# MRCS-PCR-Clinic.net
KiCad netlist of a schematic drawn in EAGLE
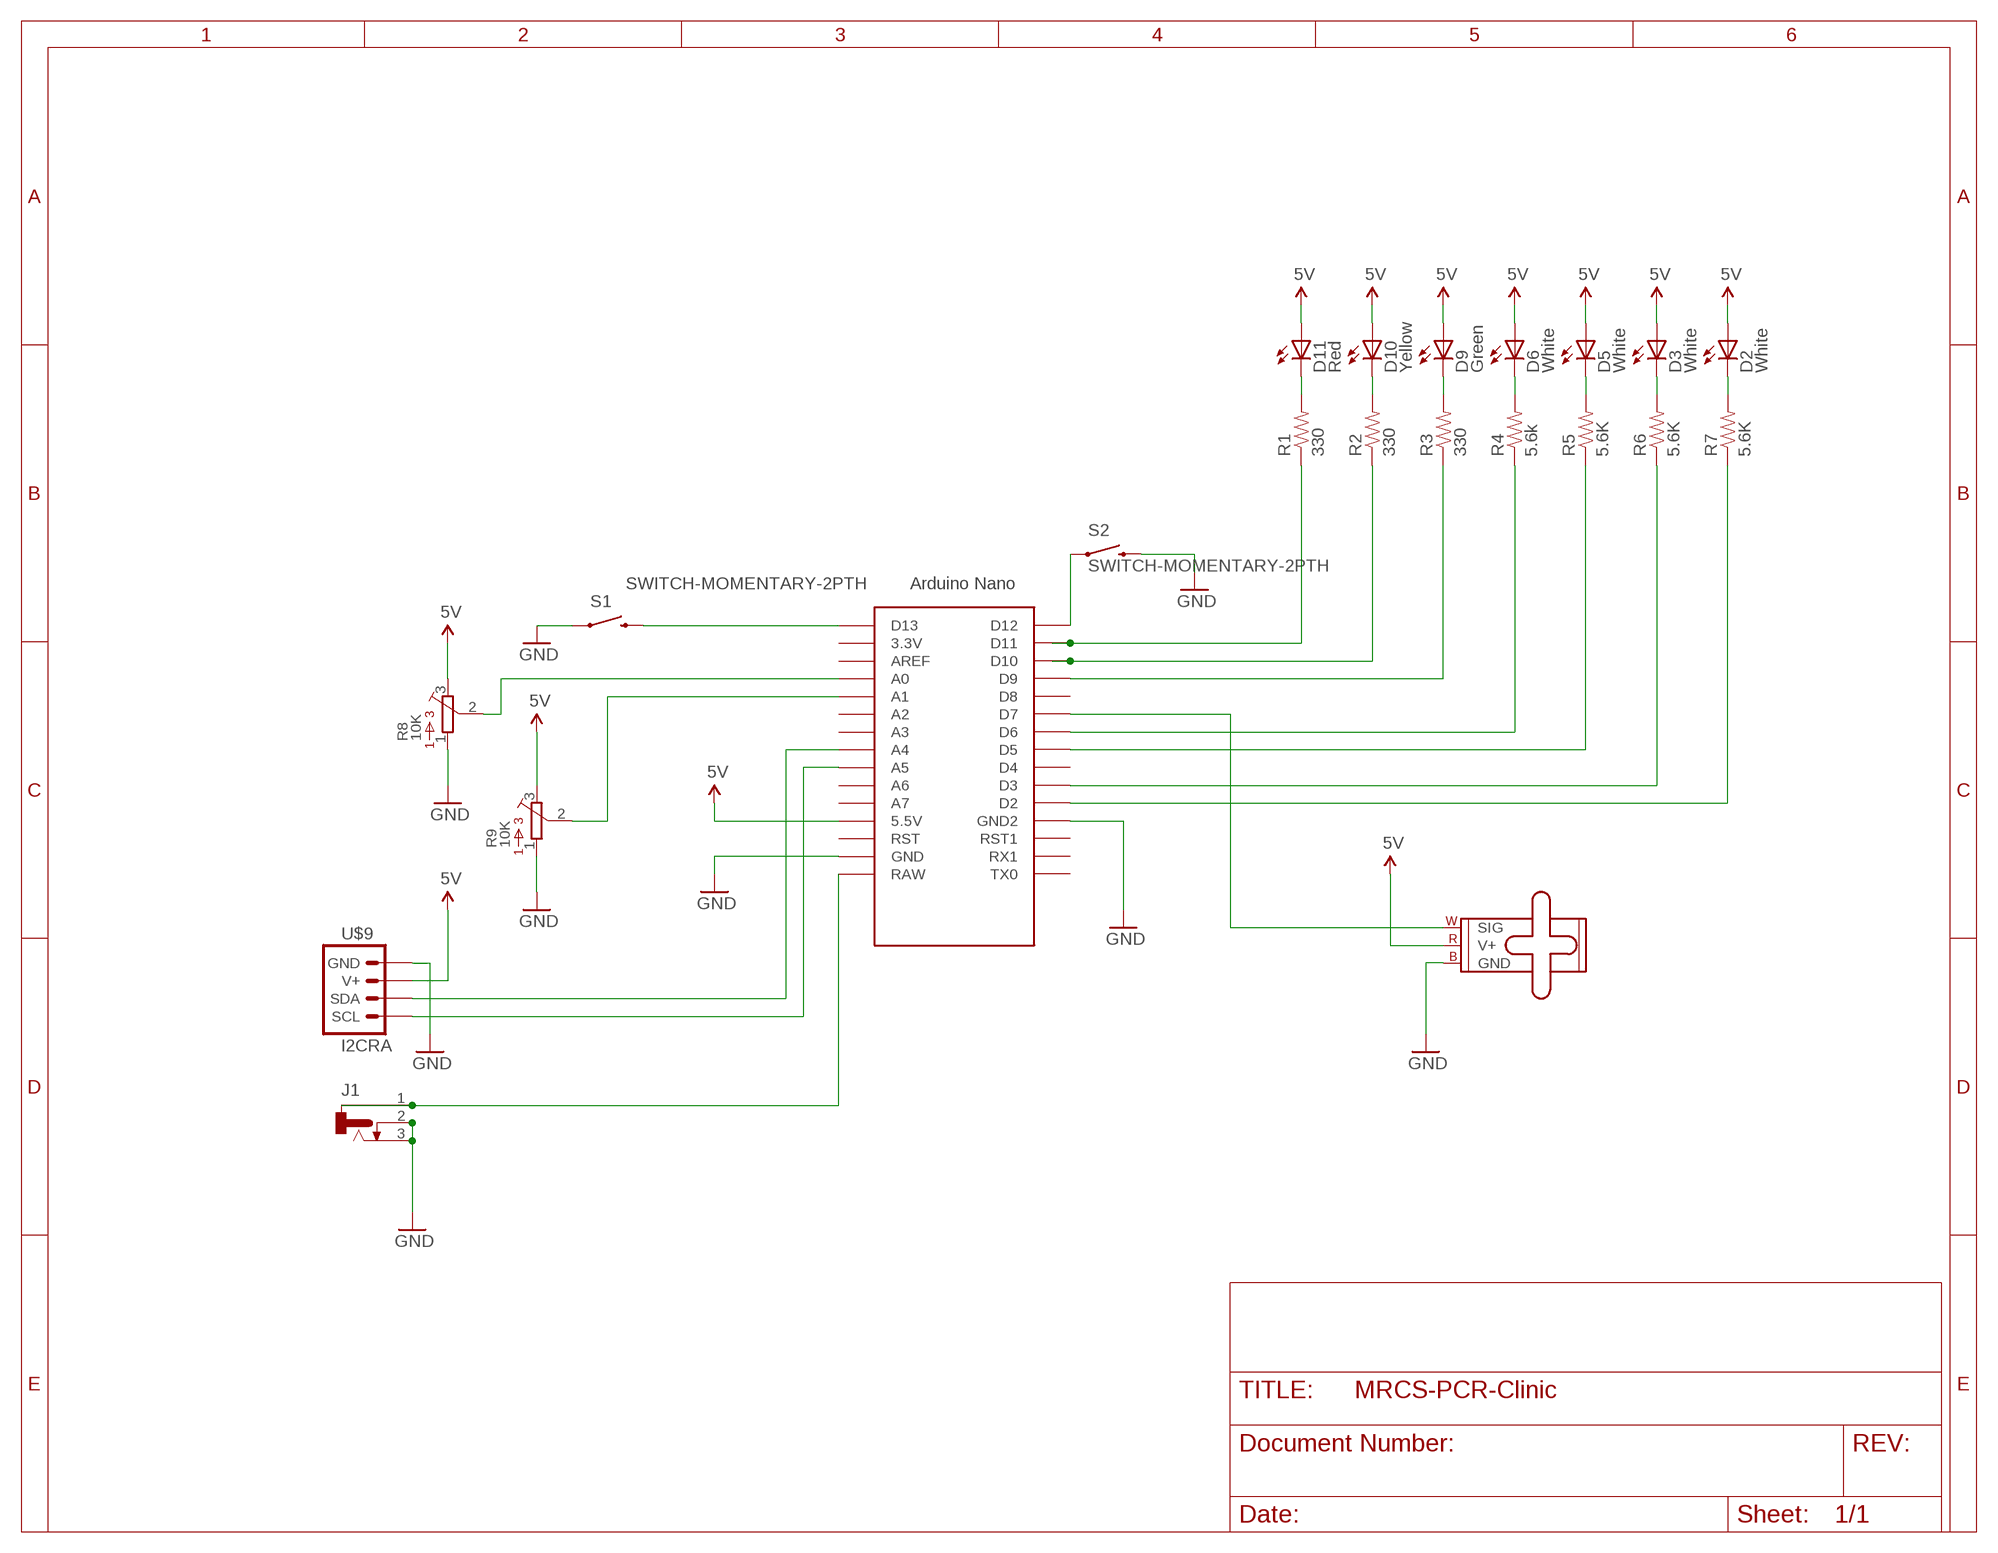
[diagram p0: schematic, sheet 1]

(export (version "E")
  (design (tool "Eeschema 10.0.6"))
  (components
    (comp (ref "D2")
      (value "White")
      (footprint "eagle-import:LED3MM")
      (libsource (lib "eagle-import") (part "LEDLED3MM"))
    )
    (comp (ref "D3")
      (value "White")
      (footprint "eagle-import:LED3MM")
      (libsource (lib "eagle-import") (part "LEDLED3MM"))
    )
    (comp (ref "D5")
      (value "White")
      (footprint "eagle-import:LED3MM")
      (libsource (lib "eagle-import") (part "LEDLED3MM"))
    )
    (comp (ref "D6")
      (value "White")
      (footprint "eagle-import:LED3MM")
      (libsource (lib "eagle-import") (part "LEDLED3MM"))
    )
    (comp (ref "D9")
      (value "Green")
      (footprint "eagle-import:LED3MM")
      (libsource (lib "eagle-import") (part "LEDLED3MM"))
    )
    (comp (ref "D10")
      (value "Yellow")
      (footprint "eagle-import:LED3MM")
      (libsource (lib "eagle-import") (part "LEDLED3MM"))
    )
    (comp (ref "D11")
      (value "Red")
      (footprint "eagle-import:LED3MM")
      (libsource (lib "eagle-import") (part "LEDLED3MM"))
    )
    (comp (ref "J1")
      (value "CONNECTOR-DC-POWER-RA")
      (footprint "eagle-import:DCJ0202")
      (libsource (lib "eagle-import") (part "CONNECTOR-DC-POWER-RA"))
    )
    (comp (ref "M2")
      (value "SMALL_SERVO")
      (footprint "eagle-import:1X03")
      (libsource (lib "eagle-import") (part "SMALL_SERVO"))
    )
    (comp (ref "R1")
      (value "330")
      (footprint "eagle-import:AXIAL-0.4")
      (libsource (lib "eagle-import") (part "RESISTORPTH-1/4W"))
    )
    (comp (ref "R2")
      (value "330")
      (footprint "eagle-import:AXIAL-0.4")
      (libsource (lib "eagle-import") (part "RESISTORPTH-1/4W"))
    )
    (comp (ref "R3")
      (value "330")
      (footprint "eagle-import:AXIAL-0.4")
      (libsource (lib "eagle-import") (part "RESISTORPTH-1/4W"))
    )
    (comp (ref "R4")
      (value "5.6k")
      (footprint "eagle-import:AXIAL-0.4")
      (libsource (lib "eagle-import") (part "RESISTORPTH-1/4W"))
    )
    (comp (ref "R5")
      (value "5.6K")
      (footprint "eagle-import:AXIAL-0.4")
      (libsource (lib "eagle-import") (part "RESISTORPTH-1/4W"))
    )
    (comp (ref "R6")
      (value "5.6K")
      (footprint "eagle-import:AXIAL-0.4")
      (libsource (lib "eagle-import") (part "RESISTORPTH-1/4W"))
    )
    (comp (ref "R7")
      (value "5.6K")
      (footprint "eagle-import:AXIAL-0.4")
      (libsource (lib "eagle-import") (part "RESISTORPTH-1/4W"))
    )
    (comp (ref "R8")
      (value "10K")
      (footprint "eagle-import:3386P")
      (libsource (lib "eagle-import") (part "3386-P"))
    )
    (comp (ref "R9")
      (value "10K")
      (footprint "eagle-import:3386P")
      (libsource (lib "eagle-import") (part "3386-P"))
    )
    (comp (ref "S1")
      (value "SWITCH-MOMENTARY-2PTH")
      (footprint "eagle-import:TACTILE-PTH")
      (libsource (lib "eagle-import") (part "SWITCH-MOMENTARY-2PTH"))
    )
    (comp (ref "S2")
      (value "SWITCH-MOMENTARY-2PTH")
      (footprint "eagle-import:TACTILE-PTH")
      (libsource (lib "eagle-import") (part "SWITCH-MOMENTARY-2PTH"))
    )
    (comp (ref "U$1")
      (value "NANO")
      (footprint "eagle-import:NANO")
      (libsource (lib "eagle-import") (part "NANO"))
    )
    (comp (ref "U$9")
      (value "I2CRA")
      (footprint "eagle-import:I2C")
      (libsource (lib "eagle-import") (part "I2CRA"))
    )
  )
  (nets
    (net (code "1") (name "5V") (class "Default")
      (node (ref "D10") (pin "A") (pinfunction "A_A") (pintype "passive"))
      (node (ref "D11") (pin "A") (pinfunction "A_A") (pintype "passive"))
      (node (ref "D2") (pin "A") (pinfunction "A_A") (pintype "passive"))
      (node (ref "D3") (pin "A") (pinfunction "A_A") (pintype "passive"))
      (node (ref "D5") (pin "A") (pinfunction "A_A") (pintype "passive"))
      (node (ref "D6") (pin "A") (pinfunction "A_A") (pintype "passive"))
      (node (ref "D9") (pin "A") (pinfunction "A_A") (pintype "passive"))
      (node (ref "M2") (pin "2") (pinfunction "V+_2") (pintype "bidirectional"))
      (node (ref "R8") (pin "3") (pinfunction "3_3") (pintype "passive"))
      (node (ref "R9") (pin "3") (pinfunction "3_3") (pintype "passive"))
      (node (ref "U$1") (pin "5V") (pinfunction "5.5V_5V") (pintype "bidirectional"))
      (node (ref "U$9") (pin "V+") (pinfunction "V+_V+") (pintype "passive"))
    )
    (net (code "2") (name "GND") (class "Default")
      (node (ref "J1") (pin "2") (pinfunction "2_2") (pintype "passive"))
      (node (ref "J1") (pin "3") (pinfunction "3_3") (pintype "passive"))
      (node (ref "M2") (pin "3") (pinfunction "GND_3") (pintype "bidirectional"))
      (node (ref "R8") (pin "1") (pinfunction "1_1") (pintype "passive"))
      (node (ref "R9") (pin "1") (pinfunction "1_1") (pintype "passive"))
      (node (ref "S1") (pin "1") (pinfunction "1_1") (pintype "passive"))
      (node (ref "S2") (pin "3") (pinfunction "2_3") (pintype "passive"))
      (node (ref "U$1") (pin "GND") (pinfunction "GND_GND") (pintype "bidirectional"))
      (node (ref "U$1") (pin "GND1") (pinfunction "GND2_GND1") (pintype "bidirectional"))
      (node (ref "U$9") (pin "GND") (pinfunction "GND_GND") (pintype "passive"))
    )
    (net (code "3") (name "Net-(D2-C)") (class "Default")
      (node (ref "D2") (pin "K") (pinfunction "C_K") (pintype "passive"))
      (node (ref "R7") (pin "P$2") (pinfunction "2_P$2") (pintype "passive"))
    )
    (net (code "4") (name "Net-(D3-C)") (class "Default")
      (node (ref "D3") (pin "K") (pinfunction "C_K") (pintype "passive"))
      (node (ref "R6") (pin "P$2") (pinfunction "2_P$2") (pintype "passive"))
    )
    (net (code "5") (name "Net-(D5-C)") (class "Default")
      (node (ref "D5") (pin "K") (pinfunction "C_K") (pintype "passive"))
      (node (ref "R5") (pin "P$2") (pinfunction "2_P$2") (pintype "passive"))
    )
    (net (code "6") (name "Net-(D6-C)") (class "Default")
      (node (ref "D6") (pin "K") (pinfunction "C_K") (pintype "passive"))
      (node (ref "R4") (pin "P$2") (pinfunction "2_P$2") (pintype "passive"))
    )
    (net (code "7") (name "Net-(D9-C)") (class "Default")
      (node (ref "D9") (pin "K") (pinfunction "C_K") (pintype "passive"))
      (node (ref "R3") (pin "P$2") (pinfunction "2_P$2") (pintype "passive"))
    )
    (net (code "8") (name "Net-(D10-C)") (class "Default")
      (node (ref "D10") (pin "K") (pinfunction "C_K") (pintype "passive"))
      (node (ref "R2") (pin "P$2") (pinfunction "2_P$2") (pintype "passive"))
    )
    (net (code "9") (name "Net-(D11-C)") (class "Default")
      (node (ref "D11") (pin "K") (pinfunction "C_K") (pintype "passive"))
      (node (ref "R1") (pin "P$2") (pinfunction "2_P$2") (pintype "passive"))
    )
    (net (code "10") (name "Net-(J1-Pad1)") (class "Default")
      (node (ref "J1") (pin "1") (pinfunction "1_1") (pintype "passive"))
      (node (ref "U$1") (pin "RAW") (pinfunction "RAW_RAW") (pintype "bidirectional"))
    )
    (net (code "11") (name "Net-(M2-SIG)") (class "Default")
      (node (ref "M2") (pin "1") (pinfunction "SIG_1") (pintype "bidirectional"))
      (node (ref "U$1") (pin "D7") (pinfunction "D7_D7") (pintype "bidirectional"))
    )
    (net (code "12") (name "Net-(R1-1)") (class "Default")
      (node (ref "R1") (pin "P$1") (pinfunction "1_P$1") (pintype "passive"))
      (node (ref "U$1") (pin "D11") (pinfunction "D11_D11") (pintype "bidirectional"))
    )
    (net (code "13") (name "Net-(R2-1)") (class "Default")
      (node (ref "R2") (pin "P$1") (pinfunction "1_P$1") (pintype "passive"))
      (node (ref "U$1") (pin "D10") (pinfunction "D10_D10") (pintype "bidirectional"))
    )
    (net (code "14") (name "Net-(R3-1)") (class "Default")
      (node (ref "R3") (pin "P$1") (pinfunction "1_P$1") (pintype "passive"))
      (node (ref "U$1") (pin "D9") (pinfunction "D9_D9") (pintype "bidirectional"))
    )
    (net (code "15") (name "Net-(R4-1)") (class "Default")
      (node (ref "R4") (pin "P$1") (pinfunction "1_P$1") (pintype "passive"))
      (node (ref "U$1") (pin "D6") (pinfunction "D6_D6") (pintype "bidirectional"))
    )
    (net (code "16") (name "Net-(R5-1)") (class "Default")
      (node (ref "R5") (pin "P$1") (pinfunction "1_P$1") (pintype "passive"))
      (node (ref "U$1") (pin "D5") (pinfunction "D5_D5") (pintype "bidirectional"))
    )
    (net (code "17") (name "Net-(R6-1)") (class "Default")
      (node (ref "R6") (pin "P$1") (pinfunction "1_P$1") (pintype "passive"))
      (node (ref "U$1") (pin "D3") (pinfunction "D3_D3") (pintype "bidirectional"))
    )
    (net (code "18") (name "Net-(R7-1)") (class "Default")
      (node (ref "R7") (pin "P$1") (pinfunction "1_P$1") (pintype "passive"))
      (node (ref "U$1") (pin "D2") (pinfunction "D2_D2") (pintype "bidirectional"))
    )
    (net (code "19") (name "Net-(R8-Pad2)") (class "Default")
      (node (ref "R8") (pin "2") (pinfunction "2_2") (pintype "passive"))
      (node (ref "U$1") (pin "A0") (pinfunction "A0_A0") (pintype "bidirectional"))
    )
    (net (code "20") (name "Net-(R9-Pad2)") (class "Default")
      (node (ref "R9") (pin "2") (pinfunction "2_2") (pintype "passive"))
      (node (ref "U$1") (pin "A1") (pinfunction "A1_A1") (pintype "bidirectional"))
    )
    (net (code "21") (name "Net-(S1-2)") (class "Default")
      (node (ref "S1") (pin "3") (pinfunction "2_3") (pintype "passive"))
      (node (ref "U$1") (pin "D13") (pinfunction "D13_D13") (pintype "bidirectional"))
    )
    (net (code "22") (name "Net-(S2-Pad1)") (class "Default")
      (node (ref "S2") (pin "1") (pinfunction "1_1") (pintype "passive"))
      (node (ref "U$1") (pin "D12") (pinfunction "D12_D12") (pintype "bidirectional"))
    )
    (net (code "23") (name "Net-(U$1-PadA4)") (class "Default")
      (node (ref "U$1") (pin "A4") (pinfunction "A4_A4") (pintype "bidirectional"))
      (node (ref "U$9") (pin "SDA") (pinfunction "SDA_SDA") (pintype "passive"))
    )
    (net (code "24") (name "Net-(U$1-PadA5)") (class "Default")
      (node (ref "U$1") (pin "A5") (pinfunction "A5_A5") (pintype "bidirectional"))
      (node (ref "U$9") (pin "SCL") (pinfunction "SCL_SCL") (pintype "passive"))
    )
    (net (code "25") (name "unconnected-(U$1-Pad3.3V)") (class "Default")
      (node (ref "U$1") (pin "3.3V") (pinfunction "3.3V_3.3V") (pintype "bidirectional"))
    )
    (net (code "26") (name "unconnected-(U$1-PadA2)") (class "Default")
      (node (ref "U$1") (pin "A2") (pinfunction "A2_A2") (pintype "bidirectional"))
    )
    (net (code "27") (name "unconnected-(U$1-PadA3)") (class "Default")
      (node (ref "U$1") (pin "A3") (pinfunction "A3_A3") (pintype "bidirectional"))
    )
    (net (code "28") (name "unconnected-(U$1-PadA6)") (class "Default")
      (node (ref "U$1") (pin "A6") (pinfunction "A6_A6") (pintype "bidirectional"))
    )
    (net (code "29") (name "unconnected-(U$1-PadA7)") (class "Default")
      (node (ref "U$1") (pin "A7") (pinfunction "A7_A7") (pintype "bidirectional"))
    )
    (net (code "30") (name "unconnected-(U$1-PadAREF)") (class "Default")
      (node (ref "U$1") (pin "AREF") (pinfunction "AREF_AREF") (pintype "bidirectional"))
    )
    (net (code "31") (name "unconnected-(U$1-PadD4)") (class "Default")
      (node (ref "U$1") (pin "D4") (pinfunction "D4_D4") (pintype "bidirectional"))
    )
    (net (code "32") (name "unconnected-(U$1-PadD8)") (class "Default")
      (node (ref "U$1") (pin "D8") (pinfunction "D8_D8") (pintype "bidirectional"))
    )
    (net (code "33") (name "unconnected-(U$1-PadRST)") (class "Default")
      (node (ref "U$1") (pin "RST") (pinfunction "RST_RST") (pintype "bidirectional"))
    )
    (net (code "34") (name "unconnected-(U$1-PadRST1)") (class "Default")
      (node (ref "U$1") (pin "RST1") (pinfunction "RST1_RST1") (pintype "bidirectional"))
    )
    (net (code "35") (name "unconnected-(U$1-PadRX1)") (class "Default")
      (node (ref "U$1") (pin "RX1") (pinfunction "RX1_RX1") (pintype "bidirectional"))
    )
    (net (code "36") (name "unconnected-(U$1-PadTX0)") (class "Default")
      (node (ref "U$1") (pin "TX0") (pinfunction "TX0_TX0") (pintype "bidirectional"))
    )
  )
)
